# template_empty_board.net
KiCad netlist of a schematic drawn in EAGLE
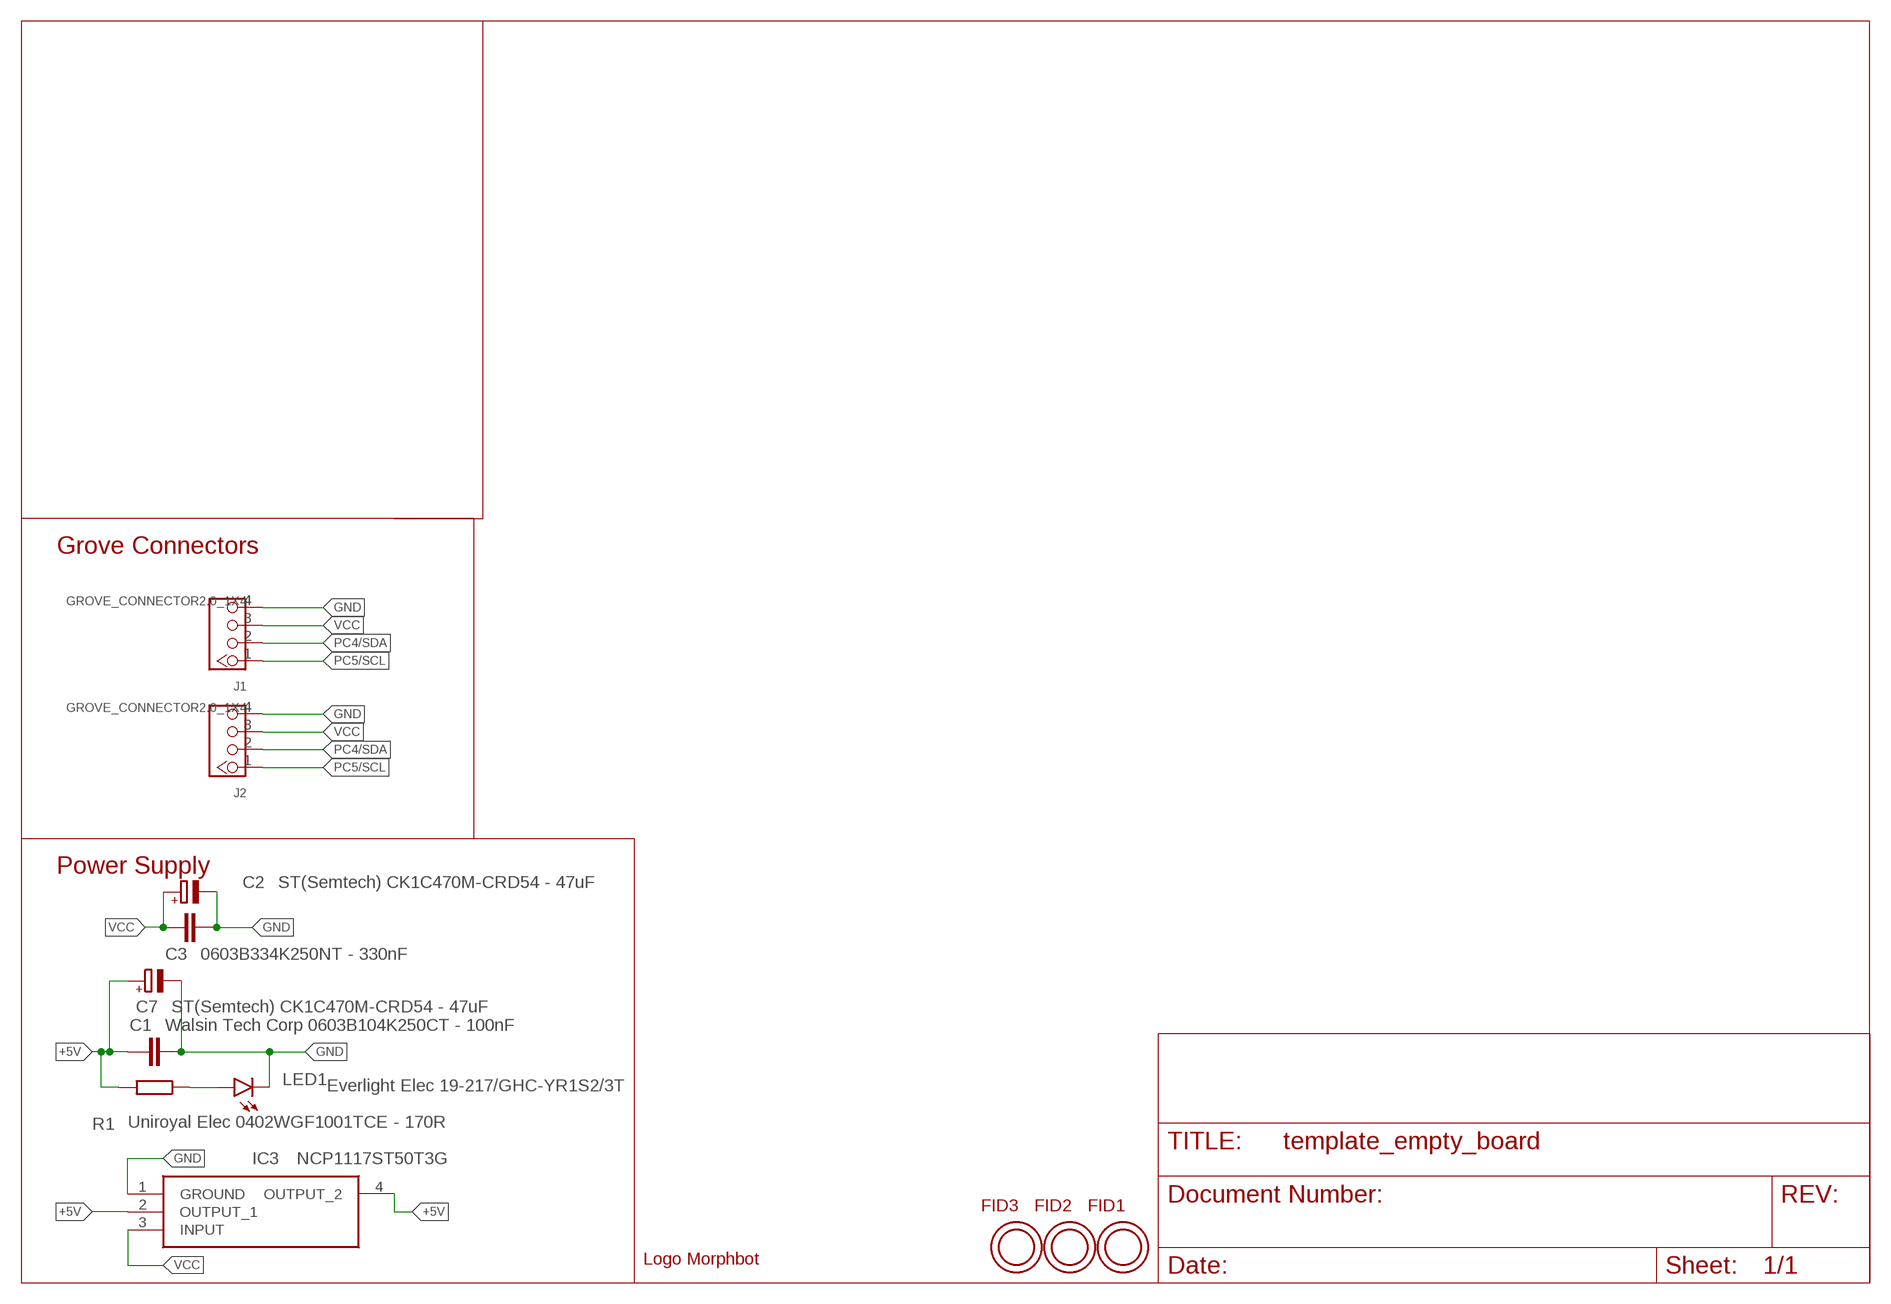
[diagram p0: schematic, sheet 1]

(export (version "E")
  (design (tool "Eeschema 10.0.6"))
  (components
    (comp (ref "C1")
      (value "Walsin Tech Corp 0603B104K250CT - 100nF")
      (footprint "eagle-import:C0603")
      (libsource (lib "eagle-import") (part "C-EUC0603"))
    )
    (comp (ref "C2")
      (value "ST(Semtech) CK1C470M-CRD54 - 47uF")
      (footprint "eagle-import:PANASONIC_C")
      (libsource (lib "eagle-import") (part "CPOL-EUC"))
    )
    (comp (ref "C3")
      (value "0603B334K250NT - 330nF")
      (footprint "eagle-import:C0603")
      (libsource (lib "eagle-import") (part "C-EUC0603"))
    )
    (comp (ref "C7")
      (value "ST(Semtech) CK1C470M-CRD54 - 47uF")
      (footprint "eagle-import:PANASONIC_C")
      (libsource (lib "eagle-import") (part "CPOL-EUC"))
    )
    (comp (ref "FID1")
      (value "OPEN-PNP-FIDUCIAL")
      (footprint "eagle-import:OPEN-PNP-FIDUCIAL")
      (libsource (lib "eagle-import") (part "OPEN-PNP-FIDUCIAL"))
    )
    (comp (ref "FID2")
      (value "OPEN-PNP-FIDUCIAL")
      (footprint "eagle-import:OPEN-PNP-FIDUCIAL")
      (libsource (lib "eagle-import") (part "OPEN-PNP-FIDUCIAL"))
    )
    (comp (ref "FID3")
      (value "OPEN-PNP-FIDUCIAL")
      (footprint "eagle-import:OPEN-PNP-FIDUCIAL")
      (libsource (lib "eagle-import") (part "OPEN-PNP-FIDUCIAL"))
    )
    (comp (ref "IC3")
      (value "NCP1117ST50T3G")
      (footprint "eagle-import:SOT230P700X180-4N")
      (fields (field (name "MOUSER_PART_NUMBER") "863-NCP1117ST50T3G"))
      (libsource (lib "eagle-import") (part "NCP1117ST50T3G"))
    )
    (comp (ref "J1")
      (value "GROVE_CONNECTOR2.0_1X4")
      (footprint "eagle-import:2.0_1X4_STRAIGHT")
      (libsource (lib "eagle-import") (part "GROVE_CONNECTOR2.0_1X4"))
    )
    (comp (ref "J2")
      (value "GROVE_CONNECTOR2.0_1X4")
      (footprint "eagle-import:2.0_1X4_STRAIGHT")
      (libsource (lib "eagle-import") (part "GROVE_CONNECTOR2.0_1X4"))
    )
    (comp (ref "LED1")
      (value "Everlight Elec 19-217/GHC-YR1S2/3T")
      (footprint "eagle-import:CHIPLED_0603")
      (libsource (lib "eagle-import") (part "LEDCHIPLED_0603"))
    )
    (comp (ref "R1")
      (value "Uniroyal Elec 0402WGF1001TCE - 170R")
      (footprint "eagle-import:R0402")
      (libsource (lib "eagle-import") (part "R-EU_R0402"))
    )
    (comp (ref "U$1")
      (value "LOGO_MORPHBOT5MM")
      (footprint "eagle-import:LOGO_MORPHBOT")
      (libsource (lib "eagle-import") (part "LOGO_MORPHBOT5MM"))
    )
  )
  (nets
    (net (code "1") (name "+5V") (class "Default")
      (node (ref "C1") (pin "1") (pinfunction "1_1") (pintype "passive"))
      (node (ref "C7") (pin "+") (pinfunction "+_+") (pintype "passive"))
      (node (ref "IC3") (pin "2") (pinfunction "OUTPUT_1_2") (pintype "bidirectional"))
      (node (ref "IC3") (pin "4") (pinfunction "OUTPUT_2_4") (pintype "bidirectional"))
      (node (ref "R1") (pin "2") (pinfunction "2_2") (pintype "passive"))
    )
    (net (code "2") (name "GND") (class "Default")
      (node (ref "C1") (pin "2") (pinfunction "2_2") (pintype "passive"))
      (node (ref "C2") (pin "-") (pinfunction "-_-") (pintype "passive"))
      (node (ref "C3") (pin "1") (pinfunction "1_1") (pintype "passive"))
      (node (ref "C7") (pin "-") (pinfunction "-_-") (pintype "passive"))
      (node (ref "IC3") (pin "1") (pinfunction "GROUND_1") (pintype "bidirectional"))
      (node (ref "J1") (pin "4") (pinfunction "4_4") (pintype "bidirectional"))
      (node (ref "J2") (pin "4") (pinfunction "4_4") (pintype "bidirectional"))
      (node (ref "LED1") (pin "C") (pinfunction "C_C") (pintype "passive"))
    )
    (net (code "3") (name "Net-(LED1-PadA)") (class "Default")
      (node (ref "LED1") (pin "A") (pinfunction "A_A") (pintype "passive"))
      (node (ref "R1") (pin "1") (pinfunction "1_1") (pintype "passive"))
    )
    (net (code "4") (name "PC4{slash}SDA") (class "Default")
      (node (ref "J1") (pin "2") (pinfunction "2_2") (pintype "bidirectional"))
      (node (ref "J2") (pin "2") (pinfunction "2_2") (pintype "bidirectional"))
    )
    (net (code "5") (name "PC5{slash}SCL") (class "Default")
      (node (ref "J1") (pin "1") (pinfunction "1_1") (pintype "bidirectional"))
      (node (ref "J2") (pin "1") (pinfunction "1_1") (pintype "bidirectional"))
    )
    (net (code "6") (name "VCC") (class "Default")
      (node (ref "C2") (pin "+") (pinfunction "+_+") (pintype "passive"))
      (node (ref "C3") (pin "2") (pinfunction "2_2") (pintype "passive"))
      (node (ref "IC3") (pin "3") (pinfunction "INPUT_3") (pintype "bidirectional"))
      (node (ref "J1") (pin "3") (pinfunction "3_3") (pintype "bidirectional"))
      (node (ref "J2") (pin "3") (pinfunction "3_3") (pintype "bidirectional"))
    )
  )
)
